# GPSpart.net
KiCad netlist of a schematic drawn in Altium Designer
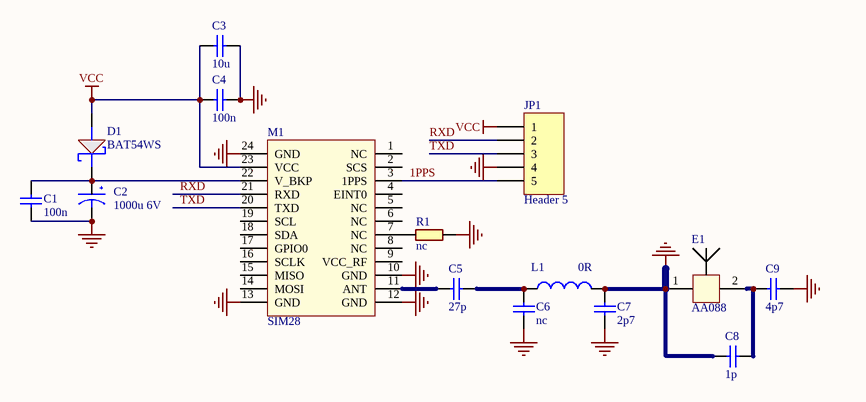
[diagram p0: GPSpart.SchDoc]

(export (version "E")
  (design (tool "Eeschema 10.0.6"))
  (components
    (comp (ref "C1") (value "100n") (footprint "CAPC1608X08N") (libsource (lib "Discrete") (part "CAPN")))
    (comp (ref "C2")
      (value "1000u 6V")
      (footprint "CAPPRD200W50D600H1250")
      (libsource (lib "Discrete") (part "C-EL-DIP"))
    )
    (comp (ref "C3") (value "10u") (footprint "CAPC2012X11N") (libsource (lib "Discrete") (part "CAPN")))
    (comp (ref "C4") (value "100n") (footprint "CAPC1608X08N") (libsource (lib "Discrete") (part "CAPN")))
    (comp (ref "C5") (value "27p") (footprint "CAPC1608X08N") (libsource (lib "Discrete") (part "CAPN")))
    (comp (ref "C6") (value "nc") (footprint "CAPC1608X08N") (libsource (lib "Discrete") (part "CAPN")))
    (comp (ref "C7") (value "2p7") (footprint "CAPC1608X08N") (libsource (lib "Discrete") (part "CAPN")))
    (comp (ref "C8") (value "1p") (footprint "CAPC1005X06N") (libsource (lib "Discrete") (part "CAPN")))
    (comp (ref "C9") (value "4p7") (footprint "CAPC1005X06N") (libsource (lib "Discrete") (part "CAPN")))
    (comp (ref "D1")
      (value "BAT54WS")
      (footprint "DIOM3216X18N")
      (libsource (lib "Discrete") (part "DIODE SCHOTTKY"))
    )
    (comp (ref "E1")
      (value "AA088")
      (footprint "CAPC3216X14N")
      (description "ceramic SMD GPS antenna")
      (libsource (lib "GPSpart") (part "AA088"))
    )
    (comp (ref "JP1")
      (value "Header 5")
      (footprint "HDRV5W70P254_5X1_1143X254H754")
      (description "Header, 5-Pin")
      (fields (field (name "PUBLISHER") "Altium Limited"))
      (libsource (lib "Miscellaneous Connectors") (part "Header 5"))
    )
    (comp (ref "L1") (value "0R") (footprint "INDC1608X10N") (libsource (lib "Discrete") (part "L")))
    (comp (ref "M1")
      (value "SIM28")
      (footprint "LGA24_GNSS")
      (libsource (lib "Cellular_GNSS") (part "SIM28"))
    )
    (comp (ref "R1") (value "nc") (footprint "RESC1608X06N") (libsource (lib "Discrete") (part "RES")))
  )
  (nets
    (net (code "1") (name "/1PPS") (class "Default")
      (node (ref "JP1") (pin "5") (pinfunction "5_5") (pintype "passive"))
      (node (ref "M1") (pin "3") (pinfunction "1PPS_3") (pintype "passive"))
    )
    (net (code "2") (name "/RXD") (class "Default")
      (node (ref "JP1") (pin "2") (pinfunction "2_2") (pintype "passive"))
      (node (ref "M1") (pin "21") (pinfunction "RXD_21") (pintype "passive"))
    )
    (net (code "3") (name "/TXD") (class "Default")
      (node (ref "JP1") (pin "3") (pinfunction "3_3") (pintype "passive"))
      (node (ref "M1") (pin "20") (pinfunction "TXD_20") (pintype "passive"))
    )
    (net (code "4") (name "GND") (class "Default")
      (node (ref "C1") (pin "2") (pinfunction "2_2") (pintype "passive"))
      (node (ref "C2") (pin "1") (pinfunction "-_1") (pintype "passive"))
      (node (ref "C3") (pin "2") (pinfunction "2_2") (pintype "passive"))
      (node (ref "C4") (pin "2") (pinfunction "2_2") (pintype "passive"))
      (node (ref "C6") (pin "2") (pinfunction "2_2") (pintype "passive"))
      (node (ref "C7") (pin "1") (pinfunction "1_1") (pintype "passive"))
      (node (ref "C7") (pin "2") (pinfunction "2_2") (pintype "passive"))
      (node (ref "C8") (pin "1") (pinfunction "1_1") (pintype "passive"))
      (node (ref "C9") (pin "1") (pinfunction "1_1") (pintype "passive"))
      (node (ref "E1") (pin "1") (pinfunction "1_1") (pintype "passive"))
      (node (ref "JP1") (pin "4") (pinfunction "4_4") (pintype "passive"))
      (node (ref "L1") (pin "2") (pinfunction "2_2") (pintype "passive"))
      (node (ref "M1") (pin "10") (pinfunction "GND_10") (pintype "passive"))
      (node (ref "M1") (pin "12") (pinfunction "GND_12") (pintype "passive"))
      (node (ref "M1") (pin "13") (pinfunction "GND_13") (pintype "passive"))
      (node (ref "M1") (pin "24") (pinfunction "GND_24") (pintype "passive"))
      (node (ref "R1") (pin "2") (pinfunction "2_2") (pintype "passive"))
    )
    (net (code "5") (name "Net-(C2-+)") (class "Default")
      (node (ref "C1") (pin "1") (pinfunction "1_1") (pintype "passive"))
      (node (ref "C2") (pin "2") (pinfunction "+_2") (pintype "passive"))
      (node (ref "D1") (pin "K") (pinfunction "K_K") (pintype "passive"))
      (node (ref "M1") (pin "22") (pinfunction "V_BKP_22") (pintype "passive"))
    )
    (net (code "6") (name "Net-(C5-Pad2)") (class "Default")
      (node (ref "C5") (pin "2") (pinfunction "2_2") (pintype "passive"))
      (node (ref "C6") (pin "1") (pinfunction "1_1") (pintype "passive"))
      (node (ref "L1") (pin "1") (pinfunction "1_1") (pintype "passive"))
    )
    (net (code "7") (name "Net-(C8-Pad2)") (class "Default")
      (node (ref "C8") (pin "2") (pinfunction "2_2") (pintype "passive"))
      (node (ref "C9") (pin "2") (pinfunction "2_2") (pintype "passive"))
      (node (ref "E1") (pin "2") (pinfunction "2_2") (pintype "passive"))
    )
    (net (code "8") (name "Net-(M1-ANT)") (class "Default")
      (node (ref "C5") (pin "1") (pinfunction "1_1") (pintype "passive"))
      (node (ref "M1") (pin "11") (pinfunction "ANT_11") (pintype "passive"))
    )
    (net (code "9") (name "Net-(M1-NC-Pad7)") (class "Default")
      (node (ref "M1") (pin "7") (pinfunction "NC_7") (pintype "passive"))
      (node (ref "R1") (pin "1") (pinfunction "1_1") (pintype "passive"))
    )
    (net (code "10") (name "VCC") (class "Default")
      (node (ref "C3") (pin "1") (pinfunction "1_1") (pintype "passive"))
      (node (ref "C4") (pin "1") (pinfunction "1_1") (pintype "passive"))
      (node (ref "D1") (pin "A") (pinfunction "A_A") (pintype "passive"))
      (node (ref "JP1") (pin "1") (pinfunction "1_1") (pintype "passive"))
      (node (ref "M1") (pin "23") (pinfunction "VCC_23") (pintype "passive"))
    )
    (net (code "11") (name "unconnected-(M1-EINT0-Pad4)") (class "Default")
      (node (ref "M1") (pin "4") (pinfunction "EINT0_4") (pintype "passive"))
    )
    (net (code "12") (name "unconnected-(M1-GPIO0-Pad17)") (class "Default")
      (node (ref "M1") (pin "17") (pinfunction "GPIO0_17") (pintype "passive"))
    )
    (net (code "13") (name "unconnected-(M1-MISO-Pad15)") (class "Default")
      (node (ref "M1") (pin "15") (pinfunction "MISO_15") (pintype "passive"))
    )
    (net (code "14") (name "unconnected-(M1-MOSI-Pad14)") (class "Default")
      (node (ref "M1") (pin "14") (pinfunction "MOSI_14") (pintype "passive"))
    )
    (net (code "15") (name "unconnected-(M1-NC-Pad1)") (class "Default")
      (node (ref "M1") (pin "1") (pinfunction "NC_1") (pintype "passive"))
    )
    (net (code "16") (name "unconnected-(M1-NC-Pad5)") (class "Default")
      (node (ref "M1") (pin "5") (pinfunction "NC_5") (pintype "passive"))
    )
    (net (code "17") (name "unconnected-(M1-NC-Pad6)") (class "Default")
      (node (ref "M1") (pin "6") (pinfunction "NC_6") (pintype "passive"))
    )
    (net (code "18") (name "unconnected-(M1-NC-Pad8)") (class "Default")
      (node (ref "M1") (pin "8") (pinfunction "NC_8") (pintype "passive"))
    )
    (net (code "19") (name "unconnected-(M1-SCL-Pad19)") (class "Default")
      (node (ref "M1") (pin "19") (pinfunction "SCL_19") (pintype "passive"))
    )
    (net (code "20") (name "unconnected-(M1-SCLK-Pad16)") (class "Default")
      (node (ref "M1") (pin "16") (pinfunction "SCLK_16") (pintype "passive"))
    )
    (net (code "21") (name "unconnected-(M1-SCS-Pad2)") (class "Default")
      (node (ref "M1") (pin "2") (pinfunction "SCS_2") (pintype "passive"))
    )
    (net (code "22") (name "unconnected-(M1-SDA-Pad18)") (class "Default")
      (node (ref "M1") (pin "18") (pinfunction "SDA_18") (pintype "passive"))
    )
    (net (code "23") (name "unconnected-(M1-VCC_RF-Pad9)") (class "Default")
      (node (ref "M1") (pin "9") (pinfunction "VCC_RF_9") (pintype "passive"))
    )
  )
)
